# 4G.net
KiCad netlist of a schematic drawn in Altium Designer
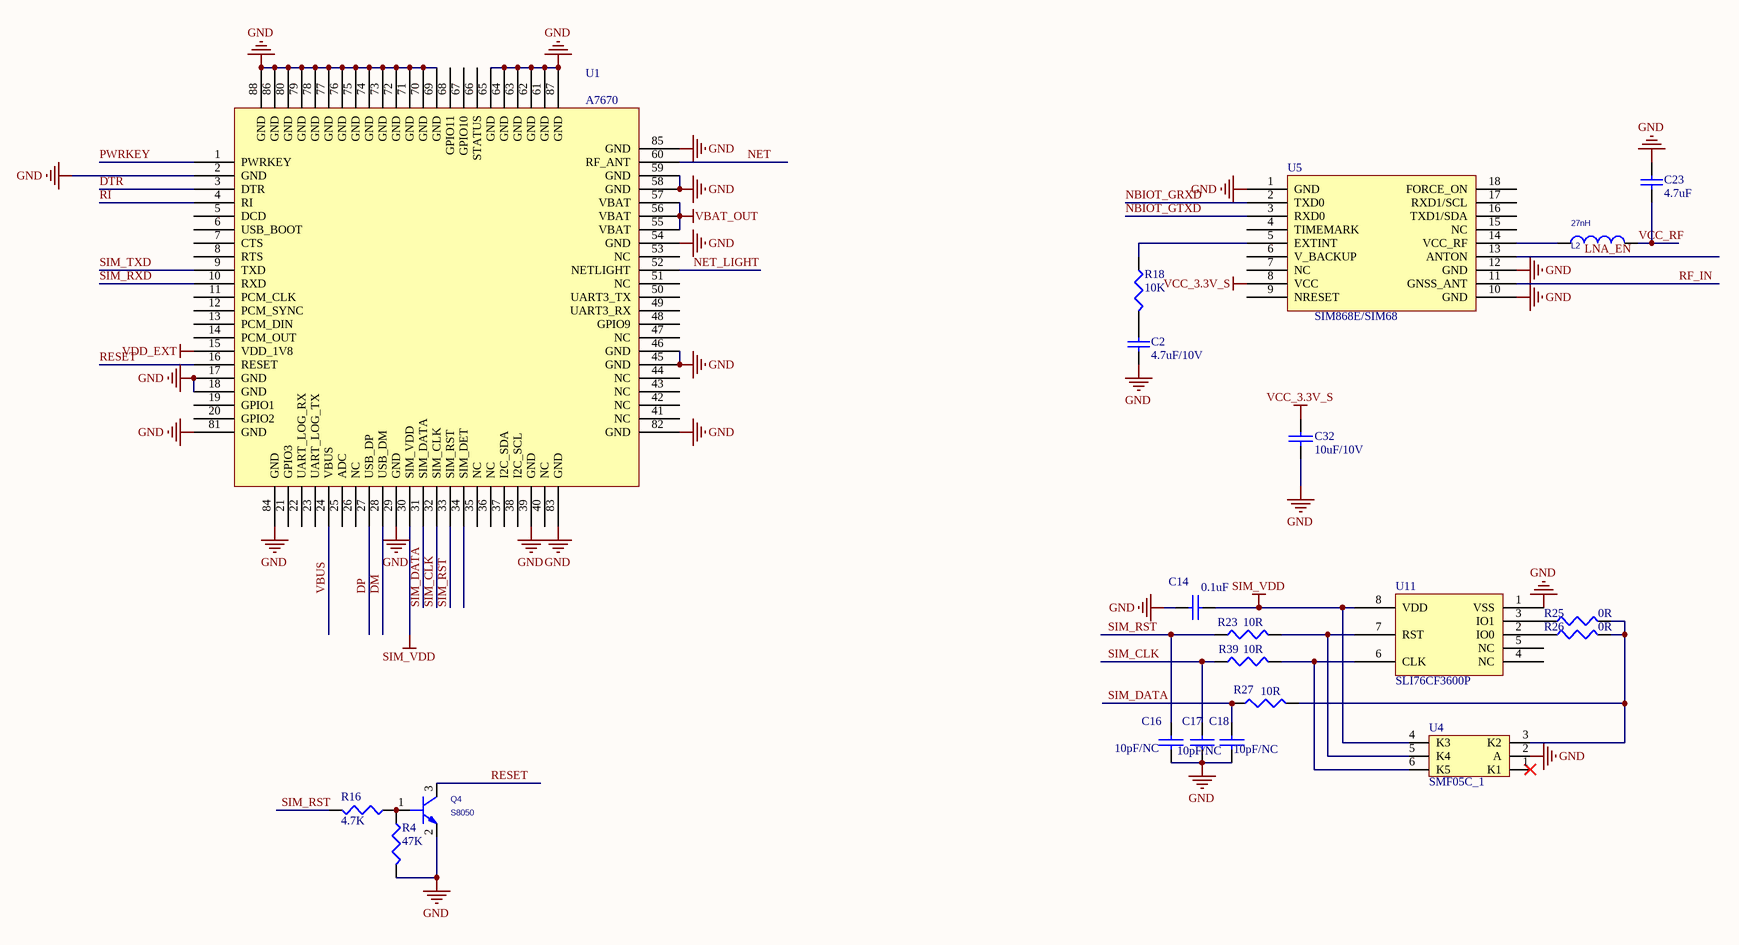
[diagram p0: 4G.SchDoc]

(export (version "E")
  (design (tool "Eeschema 10.0.6"))
  (components
    (comp (ref "C2")
      (value "4.7uF/10V")
      (footprint "0402c")
      (description "Capacitor")
      (fields (field (name "PUBLISHER") "Altium Limited"))
      (libsource (lib "Miscellaneous Devices") (part "Cap"))
    )
    (comp (ref "C14")
      (value "0.1uF")
      (footprint "0402C")
      (description "Capacitor")
      (libsource (lib "ZWLIntegrated_Library") (part "CAP"))
    )
    (comp (ref "C16")
      (value "10pF/NC")
      (footprint "0402C")
      (description "Capacitor")
      (libsource (lib "ZWLIntegrated_Library") (part "CAP"))
    )
    (comp (ref "C17")
      (value "10pF/NC")
      (footprint "0402C")
      (description "Capacitor")
      (libsource (lib "ZWLIntegrated_Library") (part "CAP"))
    )
    (comp (ref "C18")
      (value "10pF/NC")
      (footprint "0402C")
      (description "Capacitor")
      (libsource (lib "ZWLIntegrated_Library") (part "CAP"))
    )
    (comp (ref "C23")
      (value "4.7uF")
      (footprint "0402c")
      (description "Capacitor")
      (fields (field (name "PUBLISHER") "Altium Limited"))
      (libsource (lib "Miscellaneous Devices") (part "Cap"))
    )
    (comp (ref "C32")
      (value "10uF/10V")
      (footprint "0402C")
      (description "Capacitor")
      (libsource (lib "ZWLIntegrated_Library") (part "CAP"))
    )
    (comp (ref "L2") (value "27nH") (footprint "0402R") (libsource (lib "*") (part "INDUCTOR_1")))
    (comp (ref "Q4") (value "S8050") (footprint "SOT23") (libsource (lib "*") (part "2N1069_1")))
    (comp (ref "R4")
      (value "47K")
      (footprint "0402R")
      (libsource (lib "ZWLIntegrated_Library") (part "RES1"))
    )
    (comp (ref "R16")
      (value "4.7K")
      (footprint "0402R")
      (libsource (lib "ZWLIntegrated_Library") (part "RES1"))
    )
    (comp (ref "R18")
      (value "10K")
      (footprint "0402R")
      (libsource (lib "ZWLIntegrated_Library") (part "RES1"))
    )
    (comp (ref "R23")
      (value "10R")
      (footprint "0402R")
      (libsource (lib "ZWLIntegrated_Library") (part "RES1"))
    )
    (comp (ref "R25")
      (value "0R")
      (footprint "0402R")
      (libsource (lib "ZWLIntegrated_Library") (part "RES1"))
    )
    (comp (ref "R26")
      (value "0R")
      (footprint "0402R")
      (libsource (lib "ZWLIntegrated_Library") (part "RES1"))
    )
    (comp (ref "R27")
      (value "10R")
      (footprint "0402R")
      (libsource (lib "ZWLIntegrated_Library") (part "RES1"))
    )
    (comp (ref "R39")
      (value "10R")
      (footprint "0402R")
      (libsource (lib "ZWLIntegrated_Library") (part "RES1"))
    )
    (comp (ref "U1") (value "A7670") (footprint "A7670") (libsource (lib "stm32") (part "A7670")))
    (comp (ref "U4")
      (value "SMF05C_1")
      (footprint "SC70-6L")
      (description "TVS")
      (libsource (lib "SIM800C 原理图库") (part "SMF05C_1"))
    )
    (comp (ref "U5") (value "SIM868E/SIM68") (footprint "SIM68MB") (libsource (lib "stm32") (part "SIM68MB")))
    (comp (ref "U11")
      (value "SLI76CF3600P")
      (footprint "QFN127P500X600X80-8N")
      (libsource (lib "stm32") (part "SLI76CF3600P"))
    )
  )
  (nets
    (net (code "1") (name "/DM") (class "Default")
      (node (ref "U1") (pin "28") (pinfunction "USB_DM_28") (pintype "passive"))
    )
    (net (code "2") (name "/DP") (class "Default")
      (node (ref "U1") (pin "27") (pinfunction "USB_DP_27") (pintype "passive"))
    )
    (net (code "3") (name "/DTR") (class "Default")
      (node (ref "U1") (pin "3") (pinfunction "DTR_3") (pintype "passive"))
    )
    (net (code "4") (name "/LNA_EN") (class "Default")
      (node (ref "U5") (pin "13") (pinfunction "ANTON_13") (pintype "passive"))
    )
    (net (code "5") (name "/NBIOT_GRXD") (class "Default")
      (node (ref "U5") (pin "2") (pinfunction "TXD0_2") (pintype "passive"))
    )
    (net (code "6") (name "/NBIOT_GTXD") (class "Default")
      (node (ref "U5") (pin "3") (pinfunction "RXD0_3") (pintype "passive"))
    )
    (net (code "7") (name "/NET") (class "Default")
      (node (ref "U1") (pin "60") (pinfunction "RF_ANT_60") (pintype "passive"))
    )
    (net (code "8") (name "/NET_LIGHT") (class "Default")
      (node (ref "U1") (pin "52") (pinfunction "NETLIGHT_52") (pintype "passive"))
    )
    (net (code "9") (name "/PWRKEY") (class "Default")
      (node (ref "U1") (pin "1") (pinfunction "PWRKEY_1") (pintype "passive"))
    )
    (net (code "10") (name "/RESET") (class "Default")
      (node (ref "Q4") (pin "3") (pinfunction "C_3") (pintype "passive"))
      (node (ref "U1") (pin "16") (pinfunction "RESET_16") (pintype "passive"))
    )
    (net (code "11") (name "/RF_IN") (class "Default")
      (node (ref "U5") (pin "11") (pinfunction "GNSS_ANT_11") (pintype "passive"))
    )
    (net (code "12") (name "/RI") (class "Default")
      (node (ref "U1") (pin "4") (pinfunction "RI_4") (pintype "passive"))
    )
    (net (code "13") (name "/SIM_CLK") (class "Default")
      (node (ref "C17") (pin "2") (pinfunction "2_2") (pintype "passive"))
      (node (ref "R39") (pin "1") (pinfunction "1_1") (pintype "passive"))
      (node (ref "U1") (pin "32") (pinfunction "SIM_CLK_32") (pintype "passive"))
    )
    (net (code "14") (name "/SIM_DATA") (class "Default")
      (node (ref "C18") (pin "2") (pinfunction "2_2") (pintype "passive"))
      (node (ref "R27") (pin "1") (pinfunction "1_1") (pintype "passive"))
      (node (ref "U1") (pin "31") (pinfunction "SIM_DATA_31") (pintype "passive"))
    )
    (net (code "15") (name "/SIM_RST") (class "Default")
      (node (ref "C16") (pin "2") (pinfunction "2_2") (pintype "passive"))
      (node (ref "R16") (pin "2") (pinfunction "2_2") (pintype "passive"))
      (node (ref "R23") (pin "1") (pinfunction "1_1") (pintype "passive"))
      (node (ref "U1") (pin "33") (pinfunction "SIM_RST_33") (pintype "passive"))
    )
    (net (code "16") (name "/SIM_RXD") (class "Default")
      (node (ref "U1") (pin "10") (pinfunction "RXD_10") (pintype "passive"))
    )
    (net (code "17") (name "/SIM_TXD") (class "Default")
      (node (ref "U1") (pin "9") (pinfunction "TXD_9") (pintype "passive"))
    )
    (net (code "18") (name "/VBUS") (class "Default")
      (node (ref "U1") (pin "24") (pinfunction "VBUS_24") (pintype "passive"))
    )
    (net (code "19") (name "/VCC_RF") (class "Default")
      (node (ref "C23") (pin "2") (pinfunction "2_2") (pintype "passive"))
      (node (ref "L2") (pin "2") (pinfunction "2_2") (pintype "passive"))
    )
    (net (code "20") (name "GND") (class "Default")
      (node (ref "C14") (pin "1") (pinfunction "1_1") (pintype "passive"))
      (node (ref "C16") (pin "1") (pinfunction "1_1") (pintype "passive"))
      (node (ref "C17") (pin "1") (pinfunction "1_1") (pintype "passive"))
      (node (ref "C18") (pin "1") (pinfunction "1_1") (pintype "passive"))
      (node (ref "C2") (pin "1") (pinfunction "1_1") (pintype "passive"))
      (node (ref "C23") (pin "1") (pinfunction "1_1") (pintype "passive"))
      (node (ref "C32") (pin "1") (pinfunction "1_1") (pintype "passive"))
      (node (ref "Q4") (pin "2") (pinfunction "E_2") (pintype "passive"))
      (node (ref "R4") (pin "2") (pinfunction "2_2") (pintype "passive"))
      (node (ref "U1") (pin "17") (pinfunction "GND_17") (pintype "passive"))
      (node (ref "U1") (pin "18") (pinfunction "GND_18") (pintype "passive"))
      (node (ref "U1") (pin "2") (pinfunction "GND_2") (pintype "passive"))
      (node (ref "U1") (pin "29") (pinfunction "GND_29") (pintype "passive"))
      (node (ref "U1") (pin "39") (pinfunction "GND_39") (pintype "passive"))
      (node (ref "U1") (pin "45") (pinfunction "GND_45") (pintype "passive"))
      (node (ref "U1") (pin "46") (pinfunction "GND_46") (pintype "passive"))
      (node (ref "U1") (pin "54") (pinfunction "GND_54") (pintype "passive"))
      (node (ref "U1") (pin "58") (pinfunction "GND_58") (pintype "passive"))
      (node (ref "U1") (pin "59") (pinfunction "GND_59") (pintype "passive"))
      (node (ref "U1") (pin "61") (pinfunction "GND_61") (pintype "passive"))
      (node (ref "U1") (pin "62") (pinfunction "GND_62") (pintype "passive"))
      (node (ref "U1") (pin "63") (pinfunction "GND_63") (pintype "passive"))
      (node (ref "U1") (pin "64") (pinfunction "GND_64") (pintype "passive"))
      (node (ref "U1") (pin "65") (pinfunction "GND_65") (pintype "passive"))
      (node (ref "U1") (pin "69") (pinfunction "GND_69") (pintype "passive"))
      (node (ref "U1") (pin "70") (pinfunction "GND_70") (pintype "passive"))
      (node (ref "U1") (pin "71") (pinfunction "GND_71") (pintype "passive"))
      (node (ref "U1") (pin "72") (pinfunction "GND_72") (pintype "passive"))
      (node (ref "U1") (pin "73") (pinfunction "GND_73") (pintype "passive"))
      (node (ref "U1") (pin "74") (pinfunction "GND_74") (pintype "passive"))
      (node (ref "U1") (pin "75") (pinfunction "GND_75") (pintype "passive"))
      (node (ref "U1") (pin "76") (pinfunction "GND_76") (pintype "passive"))
      (node (ref "U1") (pin "77") (pinfunction "GND_77") (pintype "passive"))
      (node (ref "U1") (pin "78") (pinfunction "GND_78") (pintype "passive"))
      (node (ref "U1") (pin "79") (pinfunction "GND_79") (pintype "passive"))
      (node (ref "U1") (pin "80") (pinfunction "GND_80") (pintype "passive"))
      (node (ref "U1") (pin "81") (pinfunction "GND_81") (pintype "passive"))
      (node (ref "U1") (pin "82") (pinfunction "GND_82") (pintype "passive"))
      (node (ref "U1") (pin "83") (pinfunction "GND_83") (pintype "passive"))
      (node (ref "U1") (pin "84") (pinfunction "GND_84") (pintype "passive"))
      (node (ref "U1") (pin "85") (pinfunction "GND_85") (pintype "passive"))
      (node (ref "U1") (pin "86") (pinfunction "GND_86") (pintype "passive"))
      (node (ref "U1") (pin "87") (pinfunction "GND_87") (pintype "passive"))
      (node (ref "U1") (pin "88") (pinfunction "GND_88") (pintype "passive"))
      (node (ref "U11") (pin "1") (pinfunction "VSS_1") (pintype "passive"))
      (node (ref "U4") (pin "2") (pinfunction "A_2") (pintype "passive"))
      (node (ref "U5") (pin "1") (pinfunction "GND_1") (pintype "passive"))
      (node (ref "U5") (pin "10") (pinfunction "GND_10") (pintype "passive"))
      (node (ref "U5") (pin "12") (pinfunction "GND_12") (pintype "passive"))
    )
    (net (code "21") (name "Net-(C2-Pad2)") (class "Default")
      (node (ref "C2") (pin "2") (pinfunction "2_2") (pintype "passive"))
      (node (ref "R18") (pin "2") (pinfunction "2_2") (pintype "passive"))
    )
    (net (code "22") (name "Net-(Q4-B)") (class "Default")
      (node (ref "Q4") (pin "1") (pinfunction "B_1") (pintype "passive"))
      (node (ref "R16") (pin "1") (pinfunction "1_1") (pintype "passive"))
      (node (ref "R4") (pin "1") (pinfunction "1_1") (pintype "passive"))
    )
    (net (code "23") (name "Net-(U4-K2)") (class "Default")
      (node (ref "R25") (pin "2") (pinfunction "2_2") (pintype "passive"))
      (node (ref "R26") (pin "2") (pinfunction "2_2") (pintype "passive"))
      (node (ref "R27") (pin "2") (pinfunction "2_2") (pintype "passive"))
      (node (ref "U4") (pin "3") (pinfunction "K2_3") (pintype "passive"))
    )
    (net (code "24") (name "Net-(U5-EXTINT)") (class "Default")
      (node (ref "R18") (pin "1") (pinfunction "1_1") (pintype "passive"))
      (node (ref "U5") (pin "5") (pinfunction "EXTINT_5") (pintype "passive"))
    )
    (net (code "25") (name "Net-(U5-VCC_RF)") (class "Default")
      (node (ref "L2") (pin "1") (pinfunction "1_1") (pintype "passive"))
      (node (ref "U5") (pin "14") (pinfunction "VCC_RF_14") (pintype "passive"))
    )
    (net (code "26") (name "Net-(U11-CLK)") (class "Default")
      (node (ref "R39") (pin "2") (pinfunction "2_2") (pintype "passive"))
      (node (ref "U11") (pin "6") (pinfunction "CLK_6") (pintype "passive"))
      (node (ref "U4") (pin "6") (pinfunction "K5_6") (pintype "passive"))
    )
    (net (code "27") (name "Net-(U11-IO0)") (class "Default")
      (node (ref "R26") (pin "1") (pinfunction "1_1") (pintype "passive"))
      (node (ref "U11") (pin "2") (pinfunction "IO0_2") (pintype "passive"))
    )
    (net (code "28") (name "Net-(U11-IO1)") (class "Default")
      (node (ref "R25") (pin "1") (pinfunction "1_1") (pintype "passive"))
      (node (ref "U11") (pin "3") (pinfunction "IO1_3") (pintype "passive"))
    )
    (net (code "29") (name "Net-(U11-RST)") (class "Default")
      (node (ref "R23") (pin "2") (pinfunction "2_2") (pintype "passive"))
      (node (ref "U11") (pin "7") (pinfunction "RST_7") (pintype "passive"))
      (node (ref "U4") (pin "5") (pinfunction "K4_5") (pintype "passive"))
    )
    (net (code "30") (name "SIM_VDD") (class "Default")
      (node (ref "C14") (pin "2") (pinfunction "2_2") (pintype "passive"))
      (node (ref "U1") (pin "30") (pinfunction "SIM_VDD_30") (pintype "passive"))
      (node (ref "U11") (pin "8") (pinfunction "VDD_8") (pintype "passive"))
      (node (ref "U4") (pin "4") (pinfunction "K3_4") (pintype "passive"))
    )
    (net (code "31") (name "VBAT_OUT") (class "Default")
      (node (ref "U1") (pin "55") (pinfunction "VBAT_55") (pintype "passive"))
      (node (ref "U1") (pin "56") (pinfunction "VBAT_56") (pintype "passive"))
      (node (ref "U1") (pin "57") (pinfunction "VBAT_57") (pintype "passive"))
    )
    (net (code "32") (name "VCC_3.3V_S") (class "Default")
      (node (ref "C32") (pin "2") (pinfunction "2_2") (pintype "passive"))
      (node (ref "U5") (pin "8") (pinfunction "VCC_8") (pintype "passive"))
    )
    (net (code "33") (name "VDD_EXT") (class "Default")
      (node (ref "U1") (pin "15") (pinfunction "VDD_1V8_15") (pintype "passive"))
    )
    (net (code "34") (name "unconnected-(U1-ADC-Pad25)") (class "Default")
      (node (ref "U1") (pin "25") (pinfunction "ADC_25") (pintype "passive"))
    )
    (net (code "35") (name "unconnected-(U1-CTS-Pad7)") (class "Default")
      (node (ref "U1") (pin "7") (pinfunction "CTS_7") (pintype "passive"))
    )
    (net (code "36") (name "unconnected-(U1-DCD-Pad5)") (class "Default")
      (node (ref "U1") (pin "5") (pinfunction "DCD_5") (pintype "passive"))
    )
    (net (code "37") (name "unconnected-(U1-GPIO1-Pad19)") (class "Default")
      (node (ref "U1") (pin "19") (pinfunction "GPIO1_19") (pintype "passive"))
    )
    (net (code "38") (name "unconnected-(U1-GPIO2-Pad20)") (class "Default")
      (node (ref "U1") (pin "20") (pinfunction "GPIO2_20") (pintype "passive"))
    )
    (net (code "39") (name "unconnected-(U1-GPIO3-Pad21)") (class "Default")
      (node (ref "U1") (pin "21") (pinfunction "GPIO3_21") (pintype "passive"))
    )
    (net (code "40") (name "unconnected-(U1-GPIO9-Pad48)") (class "Default")
      (node (ref "U1") (pin "48") (pinfunction "GPIO9_48") (pintype "passive"))
    )
    (net (code "41") (name "unconnected-(U1-GPIO10-Pad67)") (class "Default")
      (node (ref "U1") (pin "67") (pinfunction "GPIO10_67") (pintype "passive"))
    )
    (net (code "42") (name "unconnected-(U1-GPIO11-Pad68)") (class "Default")
      (node (ref "U1") (pin "68") (pinfunction "GPIO11_68") (pintype "passive"))
    )
    (net (code "43") (name "unconnected-(U1-I2C_SCL-Pad38)") (class "Default")
      (node (ref "U1") (pin "38") (pinfunction "I2C_SCL_38") (pintype "passive"))
    )
    (net (code "44") (name "unconnected-(U1-I2C_SDA-Pad37)") (class "Default")
      (node (ref "U1") (pin "37") (pinfunction "I2C_SDA_37") (pintype "passive"))
    )
    (net (code "45") (name "unconnected-(U1-NC-Pad26)") (class "Default")
      (node (ref "U1") (pin "26") (pinfunction "NC_26") (pintype "passive"))
    )
    (net (code "46") (name "unconnected-(U1-NC-Pad35)") (class "Default")
      (node (ref "U1") (pin "35") (pinfunction "NC_35") (pintype "passive"))
    )
    (net (code "47") (name "unconnected-(U1-NC-Pad36)") (class "Default")
      (node (ref "U1") (pin "36") (pinfunction "NC_36") (pintype "passive"))
    )
    (net (code "48") (name "unconnected-(U1-NC-Pad40)") (class "Default")
      (node (ref "U1") (pin "40") (pinfunction "NC_40") (pintype "passive"))
    )
    (net (code "49") (name "unconnected-(U1-NC-Pad41)") (class "Default")
      (node (ref "U1") (pin "41") (pinfunction "NC_41") (pintype "passive"))
    )
    (net (code "50") (name "unconnected-(U1-NC-Pad42)") (class "Default")
      (node (ref "U1") (pin "42") (pinfunction "NC_42") (pintype "passive"))
    )
    (net (code "51") (name "unconnected-(U1-NC-Pad43)") (class "Default")
      (node (ref "U1") (pin "43") (pinfunction "NC_43") (pintype "passive"))
    )
    (net (code "52") (name "unconnected-(U1-NC-Pad44)") (class "Default")
      (node (ref "U1") (pin "44") (pinfunction "NC_44") (pintype "passive"))
    )
    (net (code "53") (name "unconnected-(U1-NC-Pad47)") (class "Default")
      (node (ref "U1") (pin "47") (pinfunction "NC_47") (pintype "passive"))
    )
    (net (code "54") (name "unconnected-(U1-NC-Pad51)") (class "Default")
      (node (ref "U1") (pin "51") (pinfunction "NC_51") (pintype "passive"))
    )
    (net (code "55") (name "unconnected-(U1-NC-Pad53)") (class "Default")
      (node (ref "U1") (pin "53") (pinfunction "NC_53") (pintype "passive"))
    )
    (net (code "56") (name "unconnected-(U1-PCM_CLK-Pad11)") (class "Default")
      (node (ref "U1") (pin "11") (pinfunction "PCM_CLK_11") (pintype "passive"))
    )
    (net (code "57") (name "unconnected-(U1-PCM_DIN-Pad13)") (class "Default")
      (node (ref "U1") (pin "13") (pinfunction "PCM_DIN_13") (pintype "passive"))
    )
    (net (code "58") (name "unconnected-(U1-PCM_OUT-Pad14)") (class "Default")
      (node (ref "U1") (pin "14") (pinfunction "PCM_OUT_14") (pintype "passive"))
    )
    (net (code "59") (name "unconnected-(U1-PCM_SYNC-Pad12)") (class "Default")
      (node (ref "U1") (pin "12") (pinfunction "PCM_SYNC_12") (pintype "passive"))
    )
    (net (code "60") (name "unconnected-(U1-RTS-Pad8)") (class "Default")
      (node (ref "U1") (pin "8") (pinfunction "RTS_8") (pintype "passive"))
    )
    (net (code "61") (name "unconnected-(U1-SIM_DET-Pad34)") (class "Default")
      (node (ref "U1") (pin "34") (pinfunction "SIM_DET_34") (pintype "passive"))
    )
    (net (code "62") (name "unconnected-(U1-STATUS-Pad66)") (class "Default")
      (node (ref "U1") (pin "66") (pinfunction "STATUS_66") (pintype "passive"))
    )
    (net (code "63") (name "unconnected-(U1-UART3_RX-Pad49)") (class "Default")
      (node (ref "U1") (pin "49") (pinfunction "UART3_RX_49") (pintype "passive"))
    )
    (net (code "64") (name "unconnected-(U1-UART3_TX-Pad50)") (class "Default")
      (node (ref "U1") (pin "50") (pinfunction "UART3_TX_50") (pintype "passive"))
    )
    (net (code "65") (name "unconnected-(U1-UART_LOG_RX-Pad22)") (class "Default")
      (node (ref "U1") (pin "22") (pinfunction "UART_LOG_RX_22") (pintype "passive"))
    )
    (net (code "66") (name "unconnected-(U1-UART_LOG_TX-Pad23)") (class "Default")
      (node (ref "U1") (pin "23") (pinfunction "UART_LOG_TX_23") (pintype "passive"))
    )
    (net (code "67") (name "unconnected-(U1-USB_BOOT-Pad6)") (class "Default")
      (node (ref "U1") (pin "6") (pinfunction "USB_BOOT_6") (pintype "passive"))
    )
    (net (code "68") (name "unconnected-(U4-K1-Pad1)") (class "Default")
      (node (ref "U4") (pin "1") (pinfunction "K1_1") (pintype "passive+no_connect"))
    )
    (net (code "69") (name "unconnected-(U5-FORCE_ON-Pad18)") (class "Default")
      (node (ref "U5") (pin "18") (pinfunction "FORCE_ON_18") (pintype "passive"))
    )
    (net (code "70") (name "unconnected-(U5-NC-Pad7)") (class "Default")
      (node (ref "U5") (pin "7") (pinfunction "NC_7") (pintype "passive"))
    )
    (net (code "71") (name "unconnected-(U5-NC-Pad15)") (class "Default")
      (node (ref "U5") (pin "15") (pinfunction "NC_15") (pintype "passive"))
    )
    (net (code "72") (name "unconnected-(U5-NRESET-Pad9)") (class "Default")
      (node (ref "U5") (pin "9") (pinfunction "NRESET_9") (pintype "passive"))
    )
    (net (code "73") (name "unconnected-(U5-RXD1{slash}SCL-Pad17)") (class "Default")
      (node (ref "U5") (pin "17") (pinfunction "RXD1/SCL_17") (pintype "passive"))
    )
    (net (code "74") (name "unconnected-(U5-TIMEMARK-Pad4)") (class "Default")
      (node (ref "U5") (pin "4") (pinfunction "TIMEMARK_4") (pintype "passive"))
    )
    (net (code "75") (name "unconnected-(U5-TXD1{slash}SDA-Pad16)") (class "Default")
      (node (ref "U5") (pin "16") (pinfunction "TXD1/SDA_16") (pintype "passive"))
    )
    (net (code "76") (name "unconnected-(U5-V_BACKUP-Pad6)") (class "Default")
      (node (ref "U5") (pin "6") (pinfunction "V_BACKUP_6") (pintype "passive"))
    )
    (net (code "77") (name "unconnected-(U11-NC-Pad4)") (class "Default")
      (node (ref "U11") (pin "4") (pinfunction "NC_4") (pintype "passive"))
    )
    (net (code "78") (name "unconnected-(U11-NC-Pad5)") (class "Default")
      (node (ref "U11") (pin "5") (pinfunction "NC_5") (pintype "passive"))
    )
  )
)
